# Projekt91.net
KiCad netlist of a schematic drawn in Altium Designer
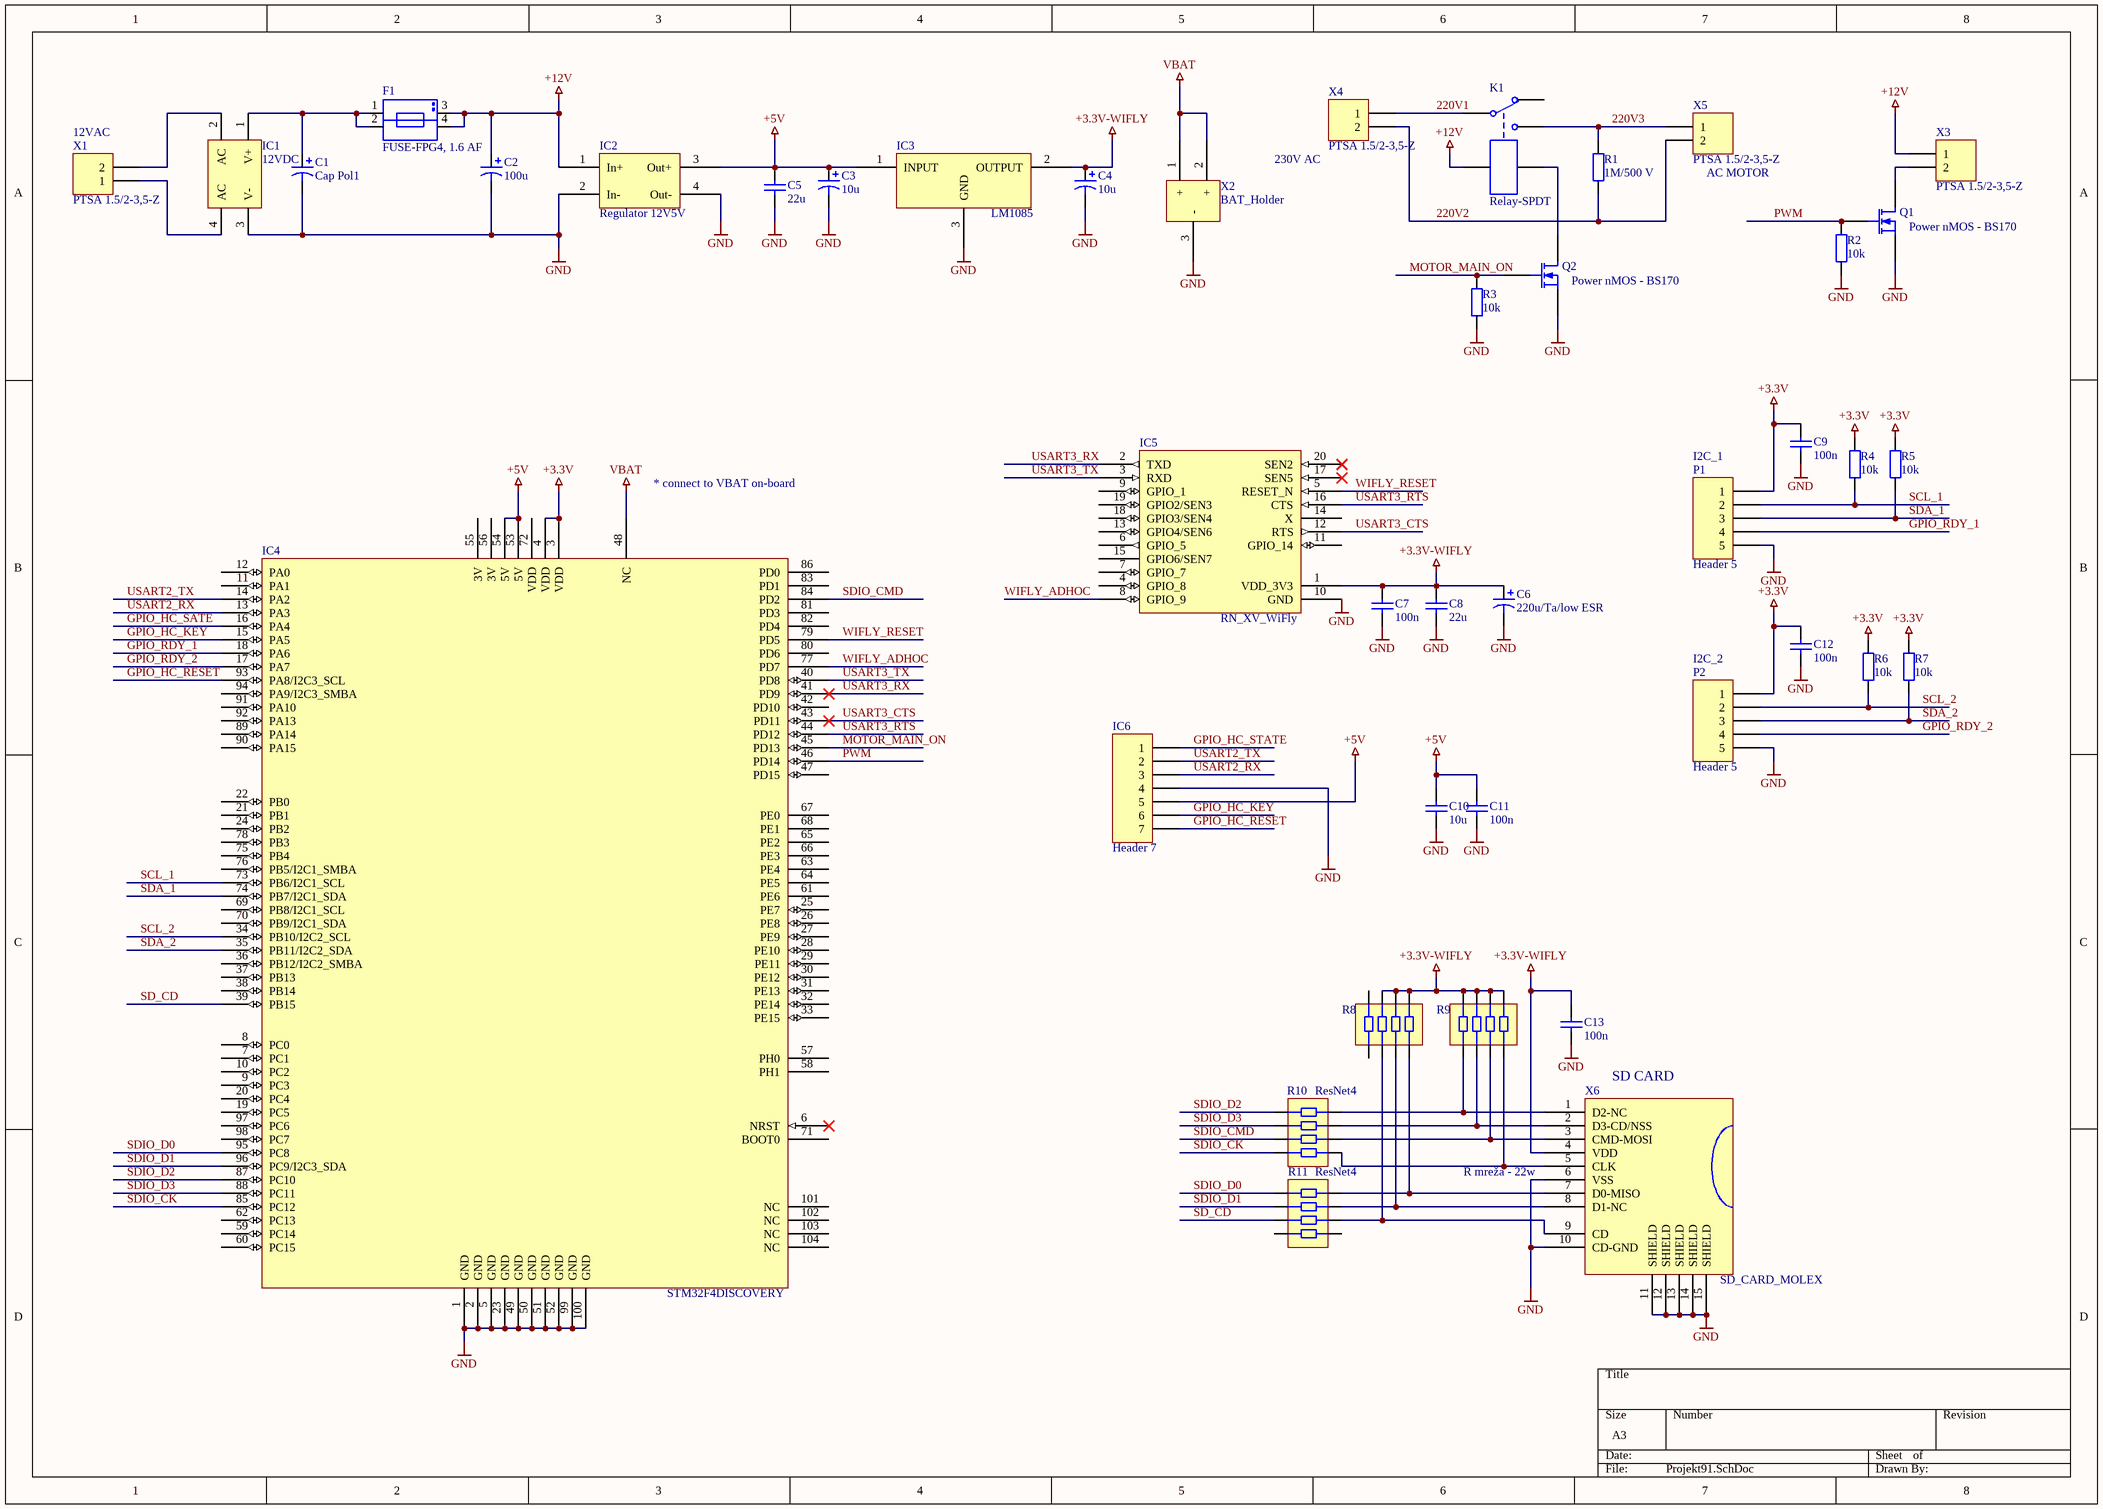
[diagram p0: Projekt91.SchDoc]

(export (version "E")
  (design (tool "Eeschema 10.0.6"))
  (components
    (comp (ref "C1")
      (value "Cap Pol1")
      (footprint "rad-5")
      (description "Polarized Capacitor (Radial)")
      (libsource (lib "Miscellaneous Devices") (part "Cap Pol1"))
    )
    (comp (ref "C2")
      (value "100u")
      (footprint "RAD-3.5")
      (description "Polarized Capacitor (Radial)")
      (libsource (lib "Miscellaneous Devices") (part "Cap Pol1"))
    )
    (comp (ref "C3")
      (value "10u")
      (footprint "C0805")
      (description "Polarized Capacitor (Surface Mount)")
      (libsource (lib "Miscellaneous Devices") (part "Cap Pol3"))
    )
    (comp (ref "C4")
      (value "10u")
      (footprint "C0805")
      (description "Polarized Capacitor (Surface Mount)")
      (libsource (lib "Miscellaneous Devices") (part "Cap Pol3"))
    )
    (comp (ref "C5")
      (value "22u")
      (footprint "C0805")
      (description "Capacitor")
      (libsource (lib "Miscellaneous Devices") (part "Cap"))
    )
    (comp (ref "C6")
      (value "220u/Ta/low ESR")
      (footprint "D_case")
      (description "Polarized Capacitor (Radial)")
      (libsource (lib "Miscellaneous Devices") (part "Cap Pol1"))
    )
    (comp (ref "C7")
      (value "100n")
      (footprint "C0805")
      (description "Capacitor")
      (libsource (lib "Miscellaneous Devices") (part "Cap"))
    )
    (comp (ref "C8")
      (value "22u")
      (footprint "C0805")
      (description "Capacitor")
      (libsource (lib "Miscellaneous Devices") (part "Cap"))
    )
    (comp (ref "C9")
      (value "100n")
      (footprint "C0805")
      (description "Capacitor")
      (libsource (lib "Miscellaneous Devices") (part "Cap"))
    )
    (comp (ref "C10")
      (value "10u")
      (footprint "c0805")
      (description "Capacitor")
      (libsource (lib "Miscellaneous Devices") (part "Cap"))
    )
    (comp (ref "C11")
      (value "100n")
      (footprint "C0805")
      (description "Capacitor")
      (libsource (lib "Miscellaneous Devices") (part "Cap"))
    )
    (comp (ref "C12")
      (value "100n")
      (footprint "C0805")
      (description "Capacitor")
      (libsource (lib "Miscellaneous Devices") (part "Cap"))
    )
    (comp (ref "C13")
      (value "100n")
      (footprint "C0805")
      (description "Capacitor")
      (libsource (lib "Miscellaneous Devices") (part "Cap"))
    )
    (comp (ref "F1")
      (value "FUSE-FPG4, 1.6 AF")
      (footprint "FUSE-FPG4")
      (libsource (lib "Projekt91") (part "FUSE-FPG4"))
    )
    (comp (ref "IC1")
      (value "12VDC")
      (footprint "graetz2")
      (description "Diode Bridge")
      (libsource (lib "Miscellaneous Devices") (part "Bridge2"))
    )
    (comp (ref "IC2")
      (value "Regulator 12V5V")
      (footprint "regulator")
      (libsource (lib "Projekt91") (part "Regulator"))
    )
    (comp (ref "IC3") (value "LM1085") (footprint "TO-220") (libsource (lib "Projekt91") (part "LM1085")))
    (comp (ref "IC4")
      (value "STM32F4DISCOVERY")
      (footprint "STM32F4DISC_BACK")
      (libsource (lib "Projekt91") (part "STM32F4DISC_w/o[101..106]"))
    )
    (comp (ref "IC5")
      (value "RN_XV_WiFly")
      (footprint "RN-XV")
      (libsource (lib "Projekt91") (part "RN_XV_WiFly"))
    )
    (comp (ref "IC6")
      (value "Header 7")
      (footprint "HDR1X7")
      (description "Header, 7-Pin")
      (libsource (lib "Miscellaneous Connectors") (part "Header 7"))
    )
    (comp (ref "K1")
      (value "Relay-SPDT")
      (footprint "relay")
      (description "Single-Pole Dual-Throw Relay")
      (libsource (lib "Miscellaneous Devices") (part "Relay-SPDT"))
    )
    (comp (ref "P1")
      (value "Header 5")
      (footprint "HDR1X5")
      (description "Header, 5-Pin")
      (libsource (lib "Miscellaneous Connectors") (part "Header 5"))
    )
    (comp (ref "P2")
      (value "Header 5")
      (footprint "HDR1X5")
      (description "Header, 5-Pin")
      (libsource (lib "Miscellaneous Connectors") (part "Header 5"))
    )
    (comp (ref "Q1")
      (value "Power nMOS - BS170")
      (footprint "to-92")
      (description "N-Channel MOSFET")
      (libsource (lib "Miscellaneous Devices") (part "MOSFET-N"))
    )
    (comp (ref "Q2")
      (value "Power nMOS - BS170")
      (footprint "to-92")
      (description "N-Channel MOSFET")
      (libsource (lib "Miscellaneous Devices") (part "MOSFET-N"))
    )
    (comp (ref "R1")
      (value "1M/500 V")
      (footprint "AXIAL-0.4")
      (description "Resistor")
      (libsource (lib "Miscellaneous Devices") (part "Res2"))
    )
    (comp (ref "R2")
      (value "10k")
      (footprint "C0805")
      (description "Resistor")
      (libsource (lib "Miscellaneous Devices") (part "Res2"))
    )
    (comp (ref "R3")
      (value "10k")
      (footprint "C0805")
      (description "Resistor")
      (libsource (lib "Miscellaneous Devices") (part "Res2"))
    )
    (comp (ref "R4")
      (value "10k")
      (footprint "C0805")
      (description "Resistor")
      (libsource (lib "Miscellaneous Devices") (part "Res2"))
    )
    (comp (ref "R5")
      (value "10k")
      (footprint "C0805")
      (description "Resistor")
      (libsource (lib "Miscellaneous Devices") (part "Res2"))
    )
    (comp (ref "R6")
      (value "10k")
      (footprint "C0805")
      (description "Resistor")
      (libsource (lib "Miscellaneous Devices") (part "Res2"))
    )
    (comp (ref "R7")
      (value "10k")
      (footprint "C0805")
      (description "Resistor")
      (libsource (lib "Miscellaneous Devices") (part "Res2"))
    )
    (comp (ref "R8") (value "ResNet4") (footprint "resnet4") (libsource (lib "Projekt91") (part "ResNet4")))
    (comp (ref "R9") (value "ResNet4") (footprint "resnet4") (libsource (lib "") (part "ResNet4_1")))
    (comp (ref "R10") (value "ResNet4") (footprint "resnet4") (libsource (lib "Projekt91") (part "ResNet4")))
    (comp (ref "R11") (value "ResNet4") (footprint "resnet4") (libsource (lib "Projekt91") (part "ResNet4")))
    (comp (ref "X1")
      (value "PTSA 1.5/2-3,5-Z")
      (footprint "PTSA_2.5MM_x2")
      (description "Header, 2-Pin")
      (libsource (lib "") (part "Header 2_1"))
    )
    (comp (ref "X2")
      (value "BAT_Holder")
      (footprint "BAT_Holder")
      (libsource (lib "Projekt91") (part "BAT_Holder"))
    )
    (comp (ref "X3")
      (value "PTSA 1.5/2-3,5-Z")
      (footprint "PTSA_2.5MM_x2")
      (description "Header, 2-Pin")
      (libsource (lib "Miscellaneous Connectors") (part "Header 2"))
    )
    (comp (ref "X4")
      (value "PTSA 1.5/2-3,5-Z")
      (footprint "PTSA_2.5MM_x2")
      (description "Header, 2-Pin")
      (libsource (lib "") (part "Header 2_2"))
    )
    (comp (ref "X5")
      (value "PTSA 1.5/2-3,5-Z")
      (footprint "PTSA_2.5MM_x2")
      (description "Header, 2-Pin")
      (libsource (lib "Miscellaneous Connectors") (part "Header 2"))
    )
    (comp (ref "X6")
      (value "SD_CARD_MOLEX")
      (footprint "MOLEX-MICROSD-503182-1853")
      (libsource (lib "Projekt91") (part "SD_CARD_MOLEX"))
    )
  )
  (nets
    (net (code "1") (name "+3.3V") (class "Default")
      (node (ref "C12") (pin "2") (pinfunction "2_2") (pintype "passive"))
      (node (ref "C9") (pin "2") (pinfunction "2_2") (pintype "passive"))
      (node (ref "IC4") (pin "3") (pinfunction "VDD_3") (pintype "power_in"))
      (node (ref "IC4") (pin "4") (pinfunction "VDD_4") (pintype "power_in"))
      (node (ref "P1") (pin "1") (pinfunction "1_1") (pintype "passive"))
      (node (ref "P2") (pin "1") (pinfunction "1_1") (pintype "passive"))
      (node (ref "R4") (pin "1") (pinfunction "1_1") (pintype "passive"))
      (node (ref "R5") (pin "1") (pinfunction "1_1") (pintype "passive"))
      (node (ref "R6") (pin "1") (pinfunction "1_1") (pintype "passive"))
      (node (ref "R7") (pin "1") (pinfunction "1_1") (pintype "passive"))
    )
    (net (code "2") (name "+3.3V-WIFLY") (class "Default")
      (node (ref "C13") (pin "2") (pinfunction "2_2") (pintype "passive"))
      (node (ref "C4") (pin "1") (pinfunction "1_1") (pintype "passive"))
      (node (ref "C6") (pin "1") (pinfunction "1_1") (pintype "passive"))
      (node (ref "C7") (pin "2") (pinfunction "2_2") (pintype "passive"))
      (node (ref "C8") (pin "2") (pinfunction "2_2") (pintype "passive"))
      (node (ref "IC3") (pin "2") (pinfunction "OUTPUT_2") (pintype "power_in"))
      (node (ref "IC5") (pin "1") (pinfunction "VDD_3V3_1") (pintype "power_in"))
      (node (ref "R8") (pin "6") (pinfunction "6_6") (pintype "passive"))
      (node (ref "R8") (pin "7") (pinfunction "7_7") (pintype "passive"))
      (node (ref "R8") (pin "8") (pinfunction "8_8") (pintype "passive"))
      (node (ref "R9") (pin "5") (pinfunction "5_5") (pintype "passive"))
      (node (ref "R9") (pin "6") (pinfunction "6_6") (pintype "passive"))
      (node (ref "R9") (pin "7") (pinfunction "7_7") (pintype "passive"))
      (node (ref "R9") (pin "8") (pinfunction "8_8") (pintype "passive"))
      (node (ref "X6") (pin "4") (pinfunction "VDD_4") (pintype "passive"))
    )
    (net (code "3") (name "+5V") (class "Default")
      (node (ref "C10") (pin "2") (pinfunction "2_2") (pintype "passive"))
      (node (ref "C11") (pin "2") (pinfunction "2_2") (pintype "passive"))
      (node (ref "C3") (pin "1") (pinfunction "1_1") (pintype "passive"))
      (node (ref "C5") (pin "2") (pinfunction "2_2") (pintype "passive"))
      (node (ref "IC2") (pin "3") (pinfunction "Out+_3") (pintype "power_in"))
      (node (ref "IC3") (pin "1") (pinfunction "INPUT_1") (pintype "power_in"))
      (node (ref "IC4") (pin "53") (pinfunction "5V_53") (pintype "power_in"))
      (node (ref "IC4") (pin "54") (pinfunction "5V_54") (pintype "power_in"))
      (node (ref "IC6") (pin "5") (pinfunction "5_5") (pintype "passive"))
    )
    (net (code "4") (name "+12V") (class "Default")
      (node (ref "C2") (pin "1") (pinfunction "1_1") (pintype "passive"))
      (node (ref "F1") (pin "3") (pintype "passive"))
      (node (ref "F1") (pin "4") (pintype "passive"))
      (node (ref "IC2") (pin "1") (pinfunction "In+_1") (pintype "power_in"))
      (node (ref "K1") (pin "4") (pinfunction "4_4") (pintype "passive"))
      (node (ref "X3") (pin "1") (pinfunction "1_1") (pintype "passive"))
    )
    (net (code "5") (name "/220V1") (class "Default")
      (node (ref "K1") (pin "1") (pinfunction "1_1") (pintype "passive"))
      (node (ref "X4") (pin "1") (pinfunction "1_1") (pintype "passive"))
    )
    (net (code "6") (name "/220V2") (class "Default")
      (node (ref "R1") (pin "2") (pinfunction "2_2") (pintype "passive"))
      (node (ref "X4") (pin "2") (pinfunction "2_2") (pintype "passive"))
      (node (ref "X5") (pin "2") (pinfunction "2_2") (pintype "passive"))
    )
    (net (code "7") (name "/220V3") (class "Default")
      (node (ref "K1") (pin "3") (pinfunction "3_3") (pintype "passive"))
      (node (ref "R1") (pin "1") (pinfunction "1_1") (pintype "passive"))
      (node (ref "X5") (pin "1") (pinfunction "1_1") (pintype "passive"))
    )
    (net (code "8") (name "/GPIO_HC_KEY") (class "Default")
      (node (ref "IC4") (pin "15") (pinfunction "PA5_15") (pintype "bidirectional"))
      (node (ref "IC6") (pin "6") (pinfunction "6_6") (pintype "passive"))
    )
    (net (code "9") (name "/GPIO_HC_RESET") (class "Default")
      (node (ref "IC4") (pin "93") (pinfunction "PA8/I2C3_SCL_93") (pintype "bidirectional"))
      (node (ref "IC6") (pin "7") (pinfunction "7_7") (pintype "passive"))
    )
    (net (code "10") (name "/GPIO_HC_SATE") (class "Default")
      (node (ref "IC4") (pin "16") (pinfunction "PA4_16") (pintype "bidirectional"))
    )
    (net (code "11") (name "/GPIO_HC_STATE") (class "Default")
      (node (ref "IC6") (pin "1") (pinfunction "1_1") (pintype "passive"))
    )
    (net (code "12") (name "/GPIO_RDY_1") (class "Default")
      (node (ref "IC4") (pin "18") (pinfunction "PA6_18") (pintype "bidirectional"))
      (node (ref "P1") (pin "4") (pinfunction "4_4") (pintype "passive"))
    )
    (net (code "13") (name "/GPIO_RDY_2") (class "Default")
      (node (ref "IC4") (pin "17") (pinfunction "PA7_17") (pintype "bidirectional"))
      (node (ref "P2") (pin "4") (pinfunction "4_4") (pintype "passive"))
    )
    (net (code "14") (name "/MOTOR_MAIN_ON") (class "Default")
      (node (ref "IC4") (pin "45") (pinfunction "PD13_45") (pintype "bidirectional"))
      (node (ref "Q2") (pin "2") (pinfunction "G_2") (pintype "passive"))
      (node (ref "R3") (pin "1") (pinfunction "1_1") (pintype "passive"))
    )
    (net (code "15") (name "/PWM") (class "Default")
      (node (ref "IC4") (pin "46") (pinfunction "PD14_46") (pintype "bidirectional"))
      (node (ref "Q1") (pin "2") (pinfunction "G_2") (pintype "passive"))
      (node (ref "R2") (pin "1") (pinfunction "1_1") (pintype "passive"))
    )
    (net (code "16") (name "/SCL_1") (class "Default")
      (node (ref "IC4") (pin "73") (pinfunction "PB6/I2C1_SCL_73") (pintype "bidirectional"))
      (node (ref "P1") (pin "2") (pinfunction "2_2") (pintype "passive"))
      (node (ref "R4") (pin "2") (pinfunction "2_2") (pintype "passive"))
    )
    (net (code "17") (name "/SCL_2") (class "Default")
      (node (ref "IC4") (pin "34") (pinfunction "PB10/I2C2_SCL_34") (pintype "bidirectional"))
      (node (ref "P2") (pin "2") (pinfunction "2_2") (pintype "passive"))
      (node (ref "R6") (pin "2") (pinfunction "2_2") (pintype "passive"))
    )
    (net (code "18") (name "/SDA_1") (class "Default")
      (node (ref "IC4") (pin "74") (pinfunction "PB7/I2C1_SDA_74") (pintype "bidirectional"))
      (node (ref "P1") (pin "3") (pinfunction "3_3") (pintype "passive"))
      (node (ref "R5") (pin "2") (pinfunction "2_2") (pintype "passive"))
    )
    (net (code "19") (name "/SDA_2") (class "Default")
      (node (ref "IC4") (pin "35") (pinfunction "PB11/I2C2_SDA_35") (pintype "bidirectional"))
      (node (ref "P2") (pin "3") (pinfunction "3_3") (pintype "passive"))
      (node (ref "R7") (pin "2") (pinfunction "2_2") (pintype "passive"))
    )
    (net (code "20") (name "/SDIO_CK") (class "Default")
      (node (ref "IC4") (pin "85") (pinfunction "PC12_85") (pintype "bidirectional"))
      (node (ref "R10") (pin "1") (pinfunction "1_1") (pintype "passive"))
    )
    (net (code "21") (name "/SDIO_CMD") (class "Default")
      (node (ref "IC4") (pin "84") (pinfunction "PD2_84") (pintype "power_in"))
      (node (ref "R10") (pin "2") (pinfunction "2_2") (pintype "passive"))
    )
    (net (code "22") (name "/SDIO_D0") (class "Default")
      (node (ref "IC4") (pin "95") (pinfunction "PC8_95") (pintype "bidirectional"))
      (node (ref "R11") (pin "4") (pinfunction "4_4") (pintype "passive"))
    )
    (net (code "23") (name "/SDIO_D1") (class "Default")
      (node (ref "IC4") (pin "96") (pinfunction "PC9/I2C3_SDA_96") (pintype "bidirectional"))
      (node (ref "R11") (pin "3") (pinfunction "3_3") (pintype "passive"))
    )
    (net (code "24") (name "/SDIO_D2") (class "Default")
      (node (ref "IC4") (pin "87") (pinfunction "PC10_87") (pintype "bidirectional"))
      (node (ref "R10") (pin "4") (pinfunction "4_4") (pintype "passive"))
    )
    (net (code "25") (name "/SDIO_D3") (class "Default")
      (node (ref "IC4") (pin "88") (pinfunction "PC11_88") (pintype "bidirectional"))
      (node (ref "R10") (pin "3") (pinfunction "3_3") (pintype "passive"))
    )
    (net (code "26") (name "/SD_CD") (class "Default")
      (node (ref "IC4") (pin "39") (pinfunction "PB15_39") (pintype "bidirectional"))
      (node (ref "R11") (pin "2") (pinfunction "2_2") (pintype "passive"))
    )
    (net (code "27") (name "/USART2_RX") (class "Default")
      (node (ref "IC4") (pin "13") (pinfunction "PA3_13") (pintype "bidirectional"))
      (node (ref "IC6") (pin "3") (pinfunction "3_3") (pintype "passive"))
    )
    (net (code "28") (name "/USART2_TX") (class "Default")
      (node (ref "IC4") (pin "14") (pinfunction "PA2_14") (pintype "bidirectional"))
      (node (ref "IC6") (pin "2") (pinfunction "2_2") (pintype "passive"))
    )
    (net (code "29") (name "/USART3_CTS") (class "Default")
      (node (ref "IC4") (pin "43") (pinfunction "PD11_43") (pintype "bidirectional"))
      (node (ref "IC5") (pin "12") (pinfunction "RTS_12") (pintype "output"))
    )
    (net (code "30") (name "/USART3_RTS") (class "Default")
      (node (ref "IC4") (pin "44") (pinfunction "PD12_44") (pintype "bidirectional"))
      (node (ref "IC5") (pin "16") (pinfunction "CTS_16") (pintype "input"))
    )
    (net (code "31") (name "/USART3_RX") (class "Default")
      (node (ref "IC4") (pin "41") (pinfunction "PD9_41") (pintype "bidirectional"))
      (node (ref "IC5") (pin "2") (pinfunction "TXD_2") (pintype "output"))
    )
    (net (code "32") (name "/USART3_TX") (class "Default")
      (node (ref "IC4") (pin "40") (pinfunction "PD8_40") (pintype "bidirectional"))
      (node (ref "IC5") (pin "3") (pinfunction "RXD_3") (pintype "input"))
    )
    (net (code "33") (name "/WIFLY_ADHOC") (class "Default")
      (node (ref "IC4") (pin "77") (pinfunction "PD7_77") (pintype "power_in"))
      (node (ref "IC5") (pin "8") (pinfunction "GPIO_9_8") (pintype "bidirectional"))
    )
    (net (code "34") (name "/WIFLY_RESET") (class "Default")
      (node (ref "IC4") (pin "79") (pinfunction "PD5_79") (pintype "power_in"))
      (node (ref "IC5") (pin "5") (pinfunction "RESET_N_5") (pintype "input"))
    )
    (net (code "35") (name "GND") (class "Default")
      (node (ref "C1") (pin "2") (pinfunction "2_2") (pintype "passive"))
      (node (ref "C10") (pin "1") (pinfunction "1_1") (pintype "passive"))
      (node (ref "C11") (pin "1") (pinfunction "1_1") (pintype "passive"))
      (node (ref "C12") (pin "1") (pinfunction "1_1") (pintype "passive"))
      (node (ref "C13") (pin "1") (pinfunction "1_1") (pintype "passive"))
      (node (ref "C2") (pin "2") (pinfunction "2_2") (pintype "passive"))
      (node (ref "C3") (pin "2") (pinfunction "2_2") (pintype "passive"))
      (node (ref "C4") (pin "2") (pinfunction "2_2") (pintype "passive"))
      (node (ref "C5") (pin "1") (pinfunction "1_1") (pintype "passive"))
      (node (ref "C6") (pin "2") (pinfunction "2_2") (pintype "passive"))
      (node (ref "C7") (pin "1") (pinfunction "1_1") (pintype "passive"))
      (node (ref "C8") (pin "1") (pinfunction "1_1") (pintype "passive"))
      (node (ref "C9") (pin "1") (pinfunction "1_1") (pintype "passive"))
      (node (ref "IC1") (pin "3") (pinfunction "V-_3") (pintype "passive"))
      (node (ref "IC2") (pin "2") (pinfunction "In-_2") (pintype "power_in"))
      (node (ref "IC2") (pin "4") (pinfunction "Out-_4") (pintype "power_in"))
      (node (ref "IC3") (pin "3") (pinfunction "GND_3") (pintype "power_in"))
      (node (ref "IC4") (pin "1") (pinfunction "GND_1") (pintype "power_in"))
      (node (ref "IC4") (pin "100") (pinfunction "GND_100") (pintype "power_in"))
      (node (ref "IC4") (pin "2") (pinfunction "GND_2") (pintype "power_in"))
      (node (ref "IC4") (pin "23") (pinfunction "GND_23") (pintype "power_in"))
      (node (ref "IC4") (pin "49") (pinfunction "GND_49") (pintype "power_in"))
      (node (ref "IC4") (pin "5") (pinfunction "GND_5") (pintype "power_in"))
      (node (ref "IC4") (pin "50") (pinfunction "GND_50") (pintype "power_in"))
      (node (ref "IC4") (pin "51") (pinfunction "GND_51") (pintype "power_in"))
      (node (ref "IC4") (pin "52") (pinfunction "GND_52") (pintype "power_in"))
      (node (ref "IC4") (pin "99") (pinfunction "GND_99") (pintype "power_in"))
      (node (ref "IC5") (pin "10") (pinfunction "GND_10") (pintype "power_in"))
      (node (ref "IC6") (pin "4") (pinfunction "4_4") (pintype "passive"))
      (node (ref "P1") (pin "5") (pinfunction "5_5") (pintype "passive"))
      (node (ref "P2") (pin "5") (pinfunction "5_5") (pintype "passive"))
      (node (ref "Q1") (pin "3") (pinfunction "S_3") (pintype "passive"))
      (node (ref "Q2") (pin "3") (pinfunction "S_3") (pintype "passive"))
      (node (ref "R2") (pin "2") (pinfunction "2_2") (pintype "passive"))
      (node (ref "R3") (pin "2") (pinfunction "2_2") (pintype "passive"))
      (node (ref "X2") (pin "3") (pinfunction "-_3") (pintype "power_in"))
      (node (ref "X6") (pin "10") (pinfunction "CD-GND_10") (pintype "passive"))
      (node (ref "X6") (pin "11") (pinfunction "SHIELD_11") (pintype "passive"))
      (node (ref "X6") (pin "12") (pinfunction "SHIELD_12") (pintype "passive"))
      (node (ref "X6") (pin "13") (pinfunction "SHIELD_13") (pintype "passive"))
      (node (ref "X6") (pin "14") (pinfunction "SHIELD_14") (pintype "passive"))
      (node (ref "X6") (pin "15") (pinfunction "SHIELD_15") (pintype "passive"))
      (node (ref "X6") (pin "6") (pinfunction "VSS_6") (pintype "passive"))
    )
    (net (code "36") (name "Net-(IC1-AC-Pad2)") (class "Default")
      (node (ref "IC1") (pin "2") (pinfunction "AC_2") (pintype "passive"))
      (node (ref "X1") (pin "2") (pinfunction "2_2") (pintype "passive"))
    )
    (net (code "37") (name "Net-(IC1-AC-Pad4)") (class "Default")
      (node (ref "IC1") (pin "4") (pinfunction "AC_4") (pintype "passive"))
      (node (ref "X1") (pin "1") (pinfunction "1_1") (pintype "passive"))
    )
    (net (code "38") (name "Net-(IC1-V+)") (class "Default")
      (node (ref "C1") (pin "1") (pinfunction "1_1") (pintype "passive"))
      (node (ref "F1") (pin "1") (pintype "passive"))
      (node (ref "F1") (pin "2") (pintype "passive"))
      (node (ref "IC1") (pin "1") (pinfunction "V+_1") (pintype "passive"))
    )
    (net (code "39") (name "Net-(Q1-D)") (class "Default")
      (node (ref "Q1") (pin "1") (pinfunction "D_1") (pintype "passive"))
      (node (ref "X3") (pin "2") (pinfunction "2_2") (pintype "passive"))
    )
    (net (code "40") (name "Net-(Q2-D)") (class "Default")
      (node (ref "K1") (pin "5") (pinfunction "5_5") (pintype "passive"))
      (node (ref "Q2") (pin "1") (pinfunction "D_1") (pintype "passive"))
    )
    (net (code "41") (name "Net-(X6-CD)") (class "Default")
      (node (ref "R11") (pin "6") (pinfunction "6_6") (pintype "passive"))
      (node (ref "R8") (pin "2") (pinfunction "2_2") (pintype "passive"))
      (node (ref "X6") (pin "9") (pinfunction "CD_9") (pintype "passive"))
    )
    (net (code "42") (name "Net-(X6-CLK)") (class "Default")
      (node (ref "R10") (pin "5") (pinfunction "5_5") (pintype "passive"))
      (node (ref "R9") (pin "1") (pinfunction "1_1") (pintype "passive"))
      (node (ref "X6") (pin "5") (pinfunction "CLK_5") (pintype "passive"))
    )
    (net (code "43") (name "Net-(X6-CMD-MOSI)") (class "Default")
      (node (ref "R10") (pin "6") (pinfunction "6_6") (pintype "passive"))
      (node (ref "R9") (pin "2") (pinfunction "2_2") (pintype "passive"))
      (node (ref "X6") (pin "3") (pinfunction "CMD-MOSI_3") (pintype "passive"))
    )
    (net (code "44") (name "Net-(X6-D0-MISO)") (class "Default")
      (node (ref "R11") (pin "8") (pinfunction "8_8") (pintype "passive"))
      (node (ref "R8") (pin "4") (pinfunction "4_4") (pintype "passive"))
      (node (ref "X6") (pin "7") (pinfunction "D0-MISO_7") (pintype "passive"))
    )
    (net (code "45") (name "Net-(X6-D1-NC)") (class "Default")
      (node (ref "R11") (pin "7") (pinfunction "7_7") (pintype "passive"))
      (node (ref "R8") (pin "3") (pinfunction "3_3") (pintype "passive"))
      (node (ref "X6") (pin "8") (pinfunction "D1-NC_8") (pintype "passive"))
    )
    (net (code "46") (name "Net-(X6-D2-NC)") (class "Default")
      (node (ref "R10") (pin "8") (pinfunction "8_8") (pintype "passive"))
      (node (ref "R9") (pin "4") (pinfunction "4_4") (pintype "passive"))
      (node (ref "X6") (pin "1") (pinfunction "D2-NC_1") (pintype "passive"))
    )
    (net (code "47") (name "Net-(X6-D3-CD{slash}NSS)") (class "Default")
      (node (ref "R10") (pin "7") (pinfunction "7_7") (pintype "passive"))
      (node (ref "R9") (pin "3") (pinfunction "3_3") (pintype "passive"))
      (node (ref "X6") (pin "2") (pinfunction "D3-CD/NSS_2") (pintype "passive"))
    )
    (net (code "48") (name "VBAT") (class "Default")
      (node (ref "IC4") (pin "48") (pinfunction "NC_48") (pintype "passive"))
      (node (ref "X2") (pin "1") (pinfunction "+_1") (pintype "power_in"))
      (node (ref "X2") (pin "2") (pinfunction "+_2") (pintype "power_in"))
    )
    (net (code "49") (name "unconnected-(IC4-3V-Pad55)") (class "Default")
      (node (ref "IC4") (pin "55") (pinfunction "3V_55") (pintype "power_in"))
    )
    (net (code "50") (name "unconnected-(IC4-3V-Pad56)") (class "Default")
      (node (ref "IC4") (pin "56") (pinfunction "3V_56") (pintype "power_in"))
    )
    (net (code "51") (name "unconnected-(IC4-BOOT0-Pad71)") (class "Default")
      (node (ref "IC4") (pin "71") (pinfunction "BOOT0_71") (pintype "power_in"))
    )
    (net (code "52") (name "unconnected-(IC4-NC-Pad101)") (class "Default")
      (node (ref "IC4") (pin "101") (pinfunction "NC_101") (pintype "tri_state"))
    )
    (net (code "53") (name "unconnected-(IC4-NC-Pad102)") (class "Default")
      (node (ref "IC4") (pin "102") (pinfunction "NC_102") (pintype "tri_state"))
    )
    (net (code "54") (name "unconnected-(IC4-NC-Pad103)") (class "Default")
      (node (ref "IC4") (pin "103") (pinfunction "NC_103") (pintype "tri_state"))
    )
    (net (code "55") (name "unconnected-(IC4-NC-Pad104)") (class "Default")
      (node (ref "IC4") (pin "104") (pinfunction "NC_104") (pintype "tri_state"))
    )
    (net (code "56") (name "unconnected-(IC4-NRST-Pad6)") (class "Default")
      (node (ref "IC4") (pin "6") (pinfunction "NRST_6") (pintype "input+no_connect"))
    )
    (net (code "57") (name "unconnected-(IC4-PA0-Pad12)") (class "Default")
      (node (ref "IC4") (pin "12") (pinfunction "PA0_12") (pintype "bidirectional"))
    )
    (net (code "58") (name "unconnected-(IC4-PA1-Pad11)") (class "Default")
      (node (ref "IC4") (pin "11") (pinfunction "PA1_11") (pintype "bidirectional"))
    )
    (net (code "59") (name "unconnected-(IC4-PA9{slash}I2C3_SMBA-Pad94)") (class "Default")
      (node (ref "IC4") (pin "94") (pinfunction "PA9/I2C3_SMBA_94") (pintype "bidirectional"))
    )
    (net (code "60") (name "unconnected-(IC4-PA10-Pad91)") (class "Default")
      (node (ref "IC4") (pin "91") (pinfunction "PA10_91") (pintype "bidirectional"))
    )
    (net (code "61") (name "unconnected-(IC4-PA13-Pad92)") (class "Default")
      (node (ref "IC4") (pin "92") (pinfunction "PA13_92") (pintype "bidirectional"))
    )
    (net (code "62") (name "unconnected-(IC4-PA14-Pad89)") (class "Default")
      (node (ref "IC4") (pin "89") (pinfunction "PA14_89") (pintype "bidirectional"))
    )
    (net (code "63") (name "unconnected-(IC4-PA15-Pad90)") (class "Default")
      (node (ref "IC4") (pin "90") (pinfunction "PA15_90") (pintype "bidirectional"))
    )
    (net (code "64") (name "unconnected-(IC4-PB0-Pad22)") (class "Default")
      (node (ref "IC4") (pin "22") (pinfunction "PB0_22") (pintype "bidirectional"))
    )
    (net (code "65") (name "unconnected-(IC4-PB1-Pad21)") (class "Default")
      (node (ref "IC4") (pin "21") (pinfunction "PB1_21") (pintype "bidirectional"))
    )
    (net (code "66") (name "unconnected-(IC4-PB2-Pad24)") (class "Default")
      (node (ref "IC4") (pin "24") (pinfunction "PB2_24") (pintype "bidirectional"))
    )
    (net (code "67") (name "unconnected-(IC4-PB3-Pad78)") (class "Default")
      (node (ref "IC4") (pin "78") (pinfunction "PB3_78") (pintype "bidirectional"))
    )
    (net (code "68") (name "unconnected-(IC4-PB4-Pad75)") (class "Default")
      (node (ref "IC4") (pin "75") (pinfunction "PB4_75") (pintype "bidirectional"))
    )
    (net (code "69") (name "unconnected-(IC4-PB5{slash}I2C1_SMBA-Pad76)") (class "Default")
      (node (ref "IC4") (pin "76") (pinfunction "PB5/I2C1_SMBA_76") (pintype "bidirectional"))
    )
    (net (code "70") (name "unconnected-(IC4-PB8{slash}I2C1_SCL-Pad69)") (class "Default")
      (node (ref "IC4") (pin "69") (pinfunction "PB8/I2C1_SCL_69") (pintype "bidirectional"))
    )
    (net (code "71") (name "unconnected-(IC4-PB9{slash}I2C1_SDA-Pad70)") (class "Default")
      (node (ref "IC4") (pin "70") (pinfunction "PB9/I2C1_SDA_70") (pintype "bidirectional"))
    )
    (net (code "72") (name "unconnected-(IC4-PB12{slash}I2C2_SMBA-Pad36)") (class "Default")
      (node (ref "IC4") (pin "36") (pinfunction "PB12/I2C2_SMBA_36") (pintype "bidirectional"))
    )
    (net (code "73") (name "unconnected-(IC4-PB13-Pad37)") (class "Default")
      (node (ref "IC4") (pin "37") (pinfunction "PB13_37") (pintype "bidirectional"))
    )
    (net (code "74") (name "unconnected-(IC4-PB14-Pad38)") (class "Default")
      (node (ref "IC4") (pin "38") (pinfunction "PB14_38") (pintype "bidirectional"))
    )
    (net (code "75") (name "unconnected-(IC4-PC0-Pad8)") (class "Default")
      (node (ref "IC4") (pin "8") (pinfunction "PC0_8") (pintype "bidirectional"))
    )
    (net (code "76") (name "unconnected-(IC4-PC1-Pad7)") (class "Default")
      (node (ref "IC4") (pin "7") (pinfunction "PC1_7") (pintype "bidirectional"))
    )
    (net (code "77") (name "unconnected-(IC4-PC2-Pad10)") (class "Default")
      (node (ref "IC4") (pin "10") (pinfunction "PC2_10") (pintype "bidirectional"))
    )
    (net (code "78") (name "unconnected-(IC4-PC3-Pad9)") (class "Default")
      (node (ref "IC4") (pin "9") (pinfunction "PC3_9") (pintype "bidirectional"))
    )
    (net (code "79") (name "unconnected-(IC4-PC4-Pad20)") (class "Default")
      (node (ref "IC4") (pin "20") (pinfunction "PC4_20") (pintype "bidirectional"))
    )
    (net (code "80") (name "unconnected-(IC4-PC5-Pad19)") (class "Default")
      (node (ref "IC4") (pin "19") (pinfunction "PC5_19") (pintype "bidirectional"))
    )
    (net (code "81") (name "unconnected-(IC4-PC6-Pad97)") (class "Default")
      (node (ref "IC4") (pin "97") (pinfunction "PC6_97") (pintype "bidirectional"))
    )
    (net (code "82") (name "unconnected-(IC4-PC7-Pad98)") (class "Default")
      (node (ref "IC4") (pin "98") (pinfunction "PC7_98") (pintype "bidirectional"))
    )
    (net (code "83") (name "unconnected-(IC4-PC13-Pad62)") (class "Default")
      (node (ref "IC4") (pin "62") (pinfunction "PC13_62") (pintype "bidirectional"))
    )
    (net (code "84") (name "unconnected-(IC4-PC14-Pad59)") (class "Default")
      (node (ref "IC4") (pin "59") (pinfunction "PC14_59") (pintype "bidirectional"))
    )
    (net (code "85") (name "unconnected-(IC4-PC15-Pad60)") (class "Default")
      (node (ref "IC4") (pin "60") (pinfunction "PC15_60") (pintype "bidirectional"))
    )
    (net (code "86") (name "unconnected-(IC4-PD0-Pad86)") (class "Default")
      (node (ref "IC4") (pin "86") (pinfunction "PD0_86") (pintype "power_in"))
    )
    (net (code "87") (name "unconnected-(IC4-PD1-Pad83)") (class "Default")
      (node (ref "IC4") (pin "83") (pinfunction "PD1_83") (pintype "power_in"))
    )
    (net (code "88") (name "unconnected-(IC4-PD3-Pad81)") (class "Default")
      (node (ref "IC4") (pin "81") (pinfunction "PD3_81") (pintype "power_in"))
    )
    (net (code "89") (name "unconnected-(IC4-PD4-Pad82)") (class "Default")
      (node (ref "IC4") (pin "82") (pinfunction "PD4_82") (pintype "power_in"))
    )
    (net (code "90") (name "unconnected-(IC4-PD6-Pad80)") (class "Default")
      (node (ref "IC4") (pin "80") (pinfunction "PD6_80") (pintype "power_in"))
    )
    (net (code "91") (name "unconnected-(IC4-PD10-Pad42)") (class "Default")
      (node (ref "IC4") (pin "42") (pinfunction "PD10_42") (pintype "bidirectional"))
    )
    (net (code "92") (name "unconnected-(IC4-PD15-Pad47)") (class "Default")
      (node (ref "IC4") (pin "47") (pinfunction "PD15_47") (pintype "bidirectional"))
    )
    (net (code "93") (name "unconnected-(IC4-PE0-Pad67)") (class "Default")
      (node (ref "IC4") (pin "67") (pinfunction "PE0_67") (pintype "power_in"))
    )
    (net (code "94") (name "unconnected-(IC4-PE1-Pad68)") (class "Default")
      (node (ref "IC4") (pin "68") (pinfunction "PE1_68") (pintype "power_in"))
    )
    (net (code "95") (name "unconnected-(IC4-PE2-Pad65)") (class "Default")
      (node (ref "IC4") (pin "65") (pinfunction "PE2_65") (pintype "power_in"))
    )
    (net (code "96") (name "unconnected-(IC4-PE3-Pad66)") (class "Default")
      (node (ref "IC4") (pin "66") (pinfunction "PE3_66") (pintype "power_in"))
    )
    (net (code "97") (name "unconnected-(IC4-PE4-Pad63)") (class "Default")
      (node (ref "IC4") (pin "63") (pinfunction "PE4_63") (pintype "power_in"))
    )
    (net (code "98") (name "unconnected-(IC4-PE5-Pad64)") (class "Default")
      (node (ref "IC4") (pin "64") (pinfunction "PE5_64") (pintype "power_in"))
    )
    (net (code "99") (name "unconnected-(IC4-PE6-Pad61)") (class "Default")
      (node (ref "IC4") (pin "61") (pinfunction "PE6_61") (pintype "power_in"))
    )
    (net (code "100") (name "unconnected-(IC4-PE7-Pad25)") (class "Default")
      (node (ref "IC4") (pin "25") (pinfunction "PE7_25") (pintype "bidirectional"))
    )
    (net (code "101") (name "unconnected-(IC4-PE8-Pad26)") (class "Default")
      (node (ref "IC4") (pin "26") (pinfunction "PE8_26") (pintype "bidirectional"))
    )
    (net (code "102") (name "unconnected-(IC4-PE9-Pad27)") (class "Default")
      (node (ref "IC4") (pin "27") (pinfunction "PE9_27") (pintype "bidirectional"))
    )
    (net (code "103") (name "unconnected-(IC4-PE10-Pad28)") (class "Default")
      (node (ref "IC4") (pin "28") (pinfunction "PE10_28") (pintype "bidirectional"))
    )
    (net (code "104") (name "unconnected-(IC4-PE11-Pad29)") (class "Default")
      (node (ref "IC4") (pin "29") (pinfunction "PE11_29") (pintype "bidirectional"))
    )
    (net (code "105") (name "unconnected-(IC4-PE12-Pad30)") (class "Default")
      (node (ref "IC4") (pin "30") (pinfunction "PE12_30") (pintype "bidirectional"))
    )
    (net (code "106") (name "unconnected-(IC4-PE13-Pad31)") (class "Default")
      (node (ref "IC4") (pin "31") (pinfunction "PE13_31") (pintype "bidirectional"))
    )
    (net (code "107") (name "unconnected-(IC4-PE14-Pad32)") (class "Default")
      (node (ref "IC4") (pin "32") (pinfunction "PE14_32") (pintype "bidirectional"))
    )
    (net (code "108") (name "unconnected-(IC4-PE15-Pad33)") (class "Default")
      (node (ref "IC4") (pin "33") (pinfunction "PE15_33") (pintype "bidirectional"))
    )
    (net (code "109") (name "unconnected-(IC4-PH0-Pad57)") (class "Default")
      (node (ref "IC4") (pin "57") (pinfunction "PH0_57") (pintype "power_in"))
    )
    (net (code "110") (name "unconnected-(IC4-PH1-Pad58)") (class "Default")
      (node (ref "IC4") (pin "58") (pinfunction "PH1_58") (pintype "power_in"))
    )
    (net (code "111") (name "unconnected-(IC4-VDD-Pad72)") (class "Default")
      (node (ref "IC4") (pin "72") (pinfunction "VDD_72") (pintype "power_in"))
    )
    (net (code "112") (name "unconnected-(IC5-GPIO2{slash}SEN3-Pad19)") (class "Default")
      (node (ref "IC5") (pin "19") (pinfunction "GPIO2/SEN3_19") (pintype "bidirectional"))
    )
    (net (code "113") (name "unconnected-(IC5-GPIO3{slash}SEN4-Pad18)") (class "Default")
      (node (ref "IC5") (pin "18") (pinfunction "GPIO3/SEN4_18") (pintype "bidirectional"))
    )
    (net (code "114") (name "unconnected-(IC5-GPIO4{slash}SEN6-Pad13)") (class "Default")
      (node (ref "IC5") (pin "13") (pinfunction "GPIO4/SEN6_13") (pintype "bidirectional"))
    )
    (net (code "115") (name "unconnected-(IC5-GPIO6{slash}SEN7-Pad15)") (class "Default")
      (node (ref "IC5") (pin "15") (pinfunction "GPIO6/SEN7_15") (pintype "power_in"))
    )
    (net (code "116") (name "unconnected-(IC5-GPIO_1-Pad9)") (class "Default")
      (node (ref "IC5") (pin "9") (pinfunction "GPIO_1_9") (pintype "bidirectional"))
    )
    (net (code "117") (name "unconnected-(IC5-GPIO_5-Pad6)") (class "Default")
      (node (ref "IC5") (pin "6") (pinfunction "GPIO_5_6") (pintype "output"))
    )
    (net (code "118") (name "unconnected-(IC5-GPIO_7-Pad7)") (class "Default")
      (node (ref "IC5") (pin "7") (pinfunction "GPIO_7_7") (pintype "bidirectional"))
    )
    (net (code "119") (name "unconnected-(IC5-GPIO_8-Pad4)") (class "Default")
      (node (ref "IC5") (pin "4") (pinfunction "GPIO_8_4") (pintype "bidirectional"))
    )
    (net (code "120") (name "unconnected-(IC5-GPIO_14-Pad11)") (class "Default")
      (node (ref "IC5") (pin "11") (pinfunction "GPIO_14_11") (pintype "bidirectional"))
    )
    (net (code "121") (name "unconnected-(IC5-SEN2-Pad20)") (class "Default")
      (node (ref "IC5") (pin "20") (pinfunction "SEN2_20") (pintype "input+no_connect"))
    )
    (net (code "122") (name "unconnected-(IC5-SEN5-Pad17)") (class "Default")
      (node (ref "IC5") (pin "17") (pinfunction "SEN5_17") (pintype "input+no_connect"))
    )
    (net (code "123") (name "unconnected-(IC5-X-Pad14)") (class "Default")
      (node (ref "IC5") (pin "14") (pinfunction "X_14") (pintype "tri_state"))
    )
    (net (code "124") (name "unconnected-(K1-Pad2)") (class "Default")
      (node (ref "K1") (pin "2") (pinfunction "2_2") (pintype "passive"))
    )
    (net (code "125") (name "unconnected-(R8-Pad1)") (class "Default")
      (node (ref "R8") (pin "1") (pinfunction "1_1") (pintype "passive"))
    )
    (net (code "126") (name "unconnected-(R8-Pad5)") (class "Default")
      (node (ref "R8") (pin "5") (pinfunction "5_5") (pintype "passive"))
    )
    (net (code "127") (name "unconnected-(R11-Pad1)") (class "Default")
      (node (ref "R11") (pin "1") (pinfunction "1_1") (pintype "passive"))
    )
    (net (code "128") (name "unconnected-(R11-Pad5)") (class "Default")
      (node (ref "R11") (pin "5") (pinfunction "5_5") (pintype "passive"))
    )
  )
)
